# ProPrj_Thunder_F722_Final_2024-11-16.net
KiCad netlist of a schematic drawn in EasyEDA Pro
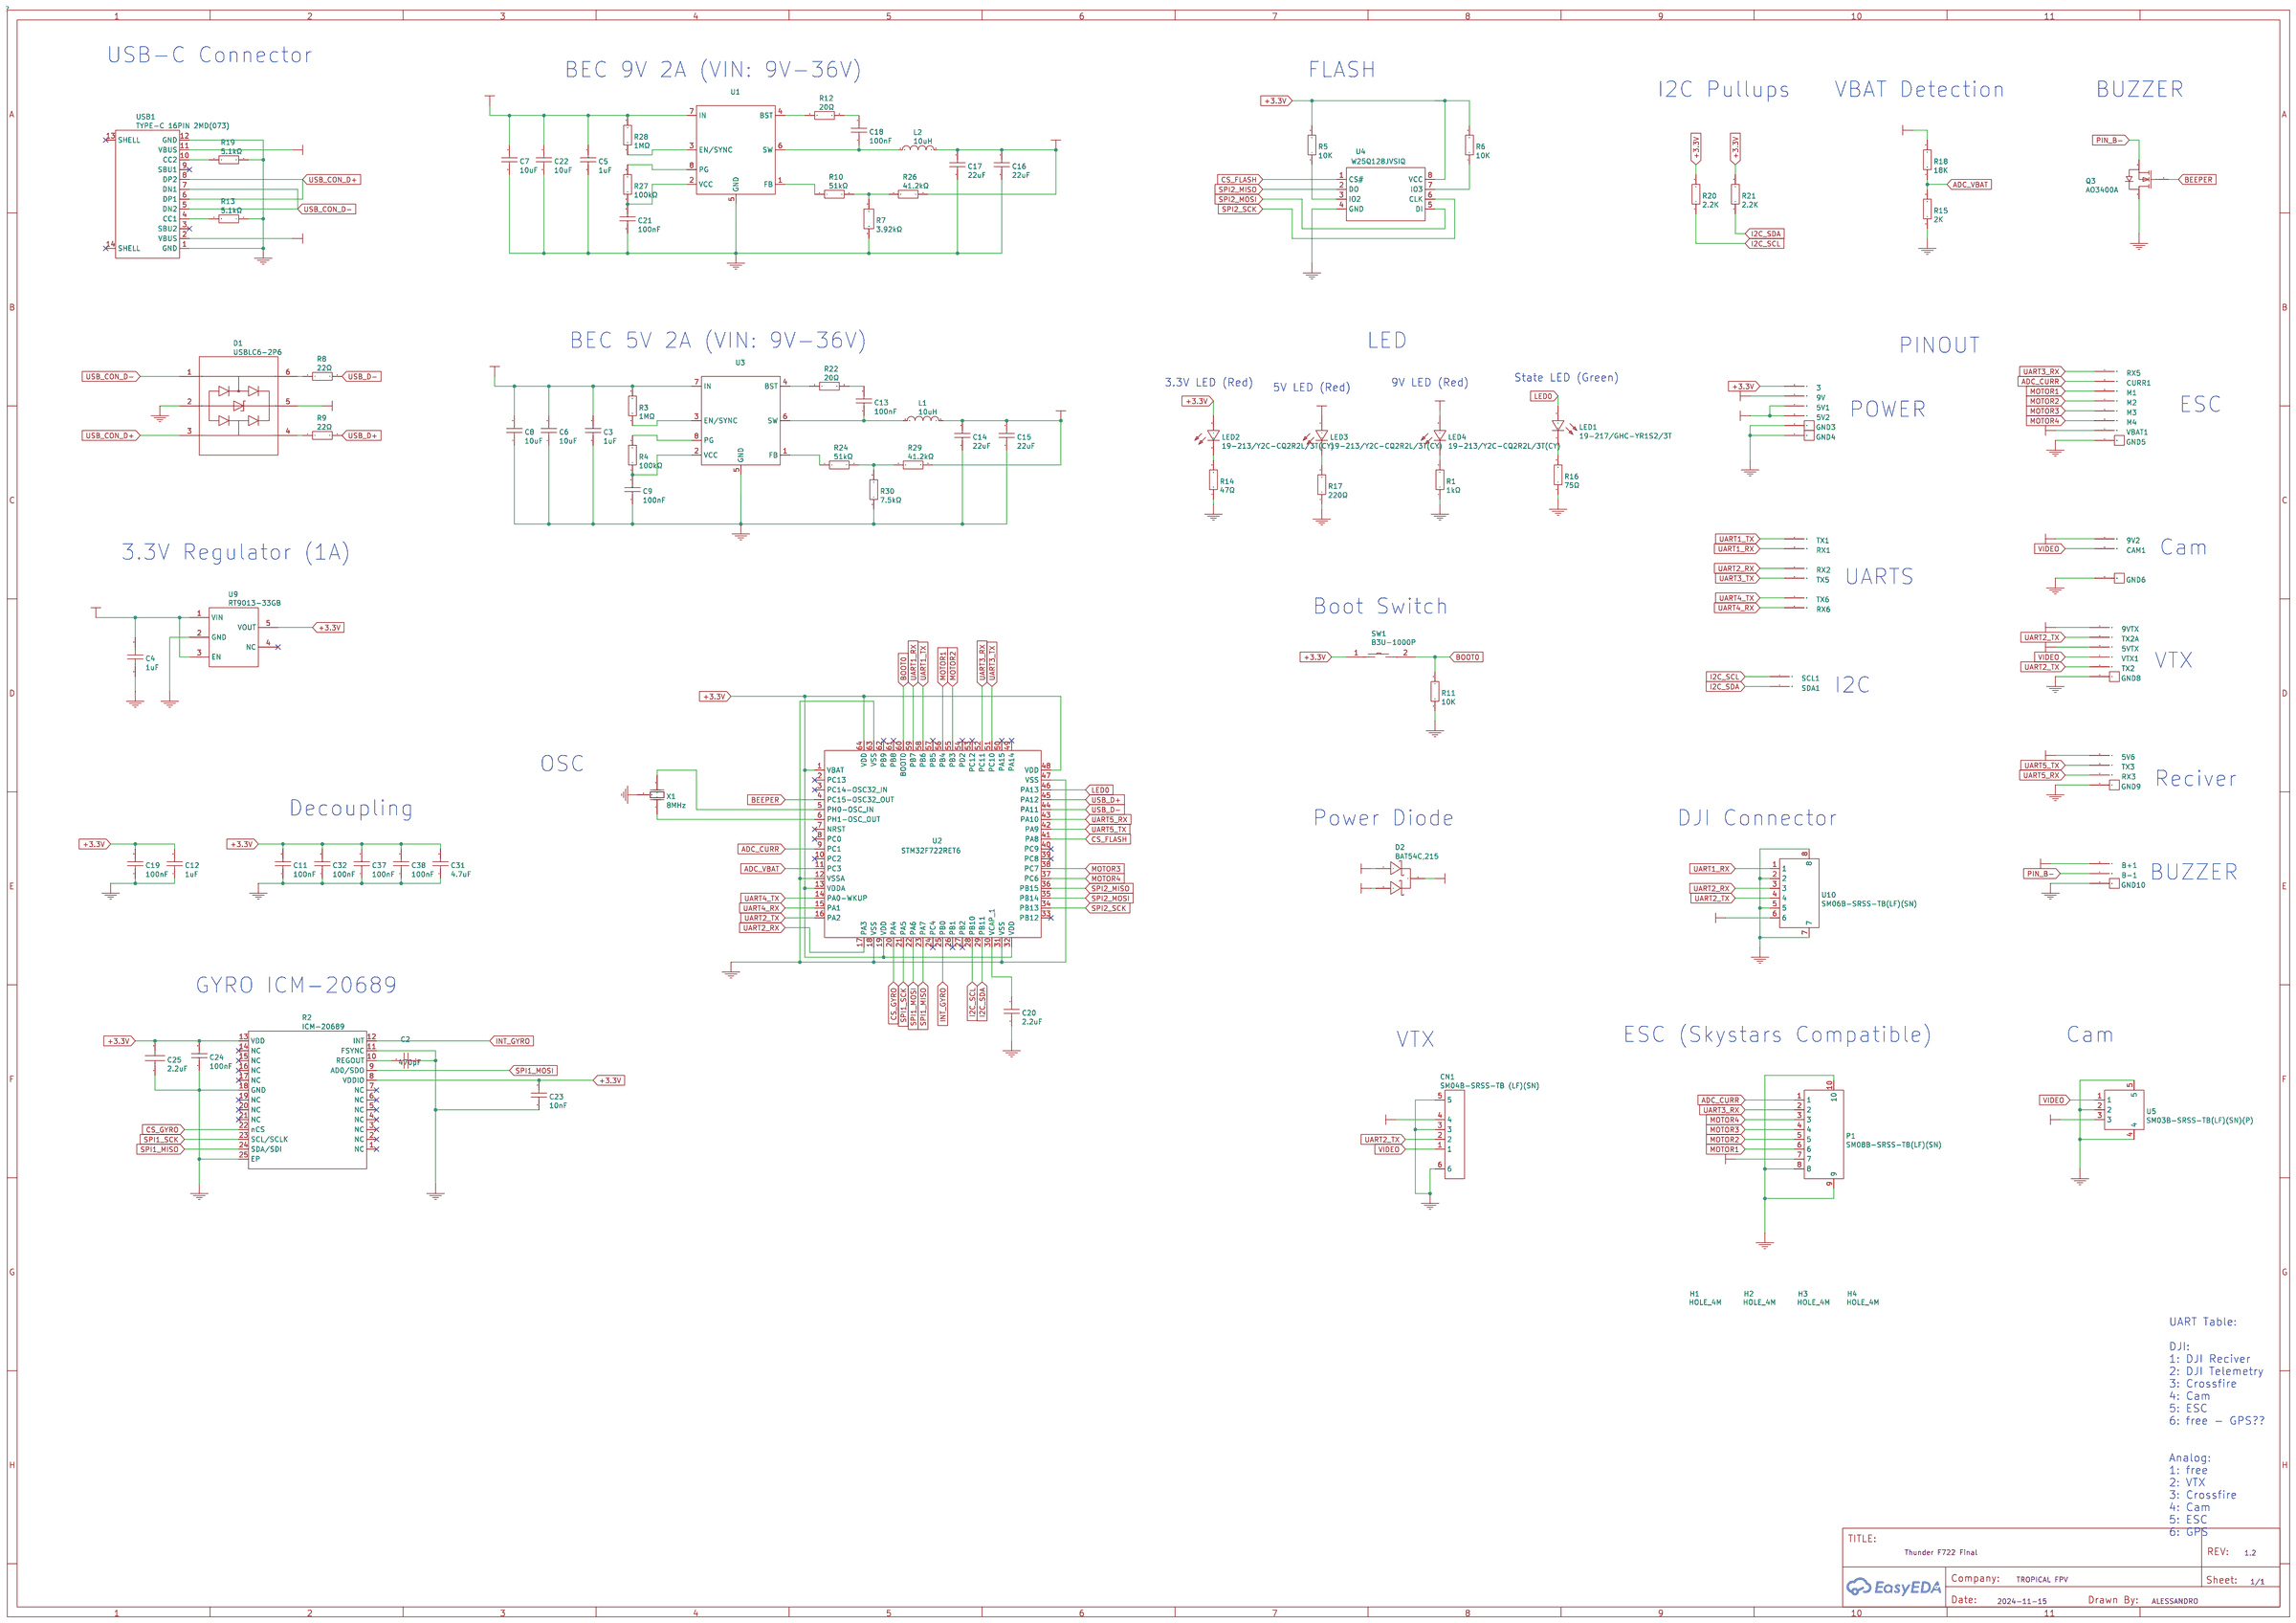
[diagram p0: schematic sheet]

(export (version "E")
  (design (tool "Eeschema 10.0.6"))
  (components
    (comp (ref "3")
      (value "ROUND SOLDER PADS WITH HOLE 1.5MM X 2.5MM COPY")
      (footprint "easyedapro:ROUND SOLDER PADS WITH HOLE 1MM X 1.75MM")
      (fields (field (name "Manufacturer Part") "solderpad"))
      (libsource (lib "easyedapro") (part "ROUND SOLDER PADS WITH HOLE 1.5MM X 2.5MM COPY"))
    )
    (comp (ref "5V1")
      (value "ROUND SOLDER PADS WITH HOLE 1.5MM X 2.5MM COPY")
      (footprint "easyedapro:ROUND SOLDER PADS WITH HOLE 1MM X 1.75MM")
      (fields (field (name "Manufacturer Part") "solderpad"))
      (libsource (lib "easyedapro") (part "ROUND SOLDER PADS WITH HOLE 1.5MM X 2.5MM COPY"))
    )
    (comp (ref "5V2")
      (value "ROUND SOLDER PADS WITH HOLE 1.5MM X 2.5MM COPY")
      (footprint "easyedapro:ROUND SOLDER PADS WITH HOLE 1MM X 1.75MM")
      (fields (field (name "Manufacturer Part") "solderpad"))
      (libsource (lib "easyedapro") (part "ROUND SOLDER PADS WITH HOLE 1.5MM X 2.5MM COPY"))
    )
    (comp (ref "5V6")
      (value "ROUND SOLDER PADS WITH HOLE 1.5MM X 2.5MM COPY")
      (footprint "easyedapro:ROUND SOLDER PADS WITH HOLE 1MM X 1.75MM")
      (fields (field (name "Manufacturer Part") "solderpad"))
      (libsource (lib "easyedapro") (part "ROUND SOLDER PADS WITH HOLE 1.5MM X 2.5MM COPY"))
    )
    (comp (ref "5VTX")
      (value "ROUND SOLDER PADS WITH HOLE 1.5MM X 2.5MM COPY")
      (footprint "easyedapro:ROUND SOLDER PADS WITH HOLE 1MM X 1.75MM")
      (fields (field (name "Manufacturer Part") "solderpad"))
      (libsource (lib "easyedapro") (part "ROUND SOLDER PADS WITH HOLE 1.5MM X 2.5MM COPY"))
    )
    (comp (ref "9V")
      (value "ROUND SOLDER PADS WITH HOLE 1.5MM X 2.5MM COPY")
      (footprint "easyedapro:ROUND SOLDER PADS WITH HOLE 1MM X 1.75MM")
      (fields (field (name "Manufacturer Part") "solderpad"))
      (libsource (lib "easyedapro") (part "ROUND SOLDER PADS WITH HOLE 1.5MM X 2.5MM COPY"))
    )
    (comp (ref "9V2")
      (value "ROUND SOLDER PADS WITH HOLE 1.5MM X 2.5MM COPY")
      (footprint "easyedapro:ROUND SOLDER PADS WITH HOLE 1MM X 1.75MM")
      (fields (field (name "Manufacturer Part") "solderpad"))
      (libsource (lib "easyedapro") (part "ROUND SOLDER PADS WITH HOLE 1.5MM X 2.5MM COPY"))
    )
    (comp (ref "9VTX")
      (value "ROUND SOLDER PADS WITH HOLE 1.5MM X 2.5MM COPY")
      (footprint "easyedapro:ROUND SOLDER PADS WITH HOLE 1MM X 1.75MM")
      (fields (field (name "Manufacturer Part") "solderpad"))
      (libsource (lib "easyedapro") (part "ROUND SOLDER PADS WITH HOLE 1.5MM X 2.5MM COPY"))
    )
    (comp (ref "B+1")
      (value "ROUND SOLDER PADS WITH HOLE 1.5MM X 2.5MM COPY")
      (footprint "easyedapro:ROUND SOLDER PADS WITH HOLE 1MM X 1.75MM")
      (fields (field (name "Manufacturer Part") "solderpad"))
      (libsource (lib "easyedapro") (part "ROUND SOLDER PADS WITH HOLE 1.5MM X 2.5MM COPY"))
    )
    (comp (ref "B-1")
      (value "ROUND SOLDER PADS WITH HOLE 1.5MM X 2.5MM COPY")
      (footprint "easyedapro:ROUND SOLDER PADS WITH HOLE 1MM X 1.75MM")
      (fields (field (name "Manufacturer Part") "solderpad"))
      (libsource (lib "easyedapro") (part "ROUND SOLDER PADS WITH HOLE 1.5MM X 2.5MM COPY"))
    )
    (comp (ref "C2")
      (value "470pF")
      (footprint "easyedapro:C0402")
      (fields (field (name "Manufacturer Part") "0402B471K500NT") (field (name "Manufacturer") "FH(风华)"))
      (libsource (lib "easyedapro") (part "470pF"))
    )
    (comp (ref "C3")
      (value "1uF")
      (footprint "easyedapro:C0603")
      (fields (field (name "Manufacturer Part") "CL10A105KB8NNNC") (field (name "Manufacturer") "SAMSUNG"))
      (libsource (lib "easyedapro") (part "1uF"))
    )
    (comp (ref "C4")
      (value "1uF")
      (footprint "easyedapro:C0402")
      (fields (field (name "Manufacturer Part") "CL05A105KA5NQNC") (field (name "Manufacturer") "SAMSUNG"))
      (libsource (lib "") (part "1uF_1"))
    )
    (comp (ref "C5")
      (value "1uF")
      (footprint "easyedapro:C0603")
      (fields (field (name "Manufacturer Part") "CL10A105KB8NNNC") (field (name "Manufacturer") "SAMSUNG"))
      (libsource (lib "easyedapro") (part "1uF"))
    )
    (comp (ref "C6")
      (value "10uF")
      (footprint "easyedapro:C1206")
      (fields (field (name "Manufacturer Part") "CL31A106KBHNNNE") (field (name "Manufacturer") "SAMSUNG"))
      (libsource (lib "easyedapro") (part "10uF"))
    )
    (comp (ref "C7")
      (value "10uF")
      (footprint "easyedapro:C1206")
      (fields (field (name "Manufacturer Part") "CL31A106KBHNNNE") (field (name "Manufacturer") "SAMSUNG"))
      (libsource (lib "easyedapro") (part "10uF"))
    )
    (comp (ref "C8")
      (value "10uF")
      (footprint "easyedapro:C1206")
      (fields (field (name "Manufacturer Part") "CL31A106KBHNNNE") (field (name "Manufacturer") "SAMSUNG"))
      (libsource (lib "easyedapro") (part "10uF"))
    )
    (comp (ref "C9")
      (value "100nF")
      (footprint "easyedapro:C0402")
      (fields (field (name "Manufacturer Part") "CL05B104KO5NNNC") (field (name "Manufacturer") "SAMSUNG"))
      (libsource (lib "easyedapro") (part "100nF"))
    )
    (comp (ref "C11")
      (value "100nF")
      (footprint "easyedapro:C0402")
      (fields (field (name "Manufacturer Part") "CL05B104KO5NNNC") (field (name "Manufacturer") "SAMSUNG"))
      (libsource (lib "easyedapro") (part "100nF"))
    )
    (comp (ref "C12")
      (value "1uF")
      (footprint "easyedapro:C0603")
      (fields (field (name "Manufacturer Part") "CL10A105KB8NNNC") (field (name "Manufacturer") "SAMSUNG"))
      (libsource (lib "easyedapro") (part "1uF"))
    )
    (comp (ref "C13")
      (value "100nF")
      (footprint "easyedapro:C0402")
      (fields (field (name "Manufacturer Part") "CL05B104KO5NNNC") (field (name "Manufacturer") "SAMSUNG"))
      (libsource (lib "easyedapro") (part "100nF"))
    )
    (comp (ref "C14")
      (value "22uF")
      (footprint "easyedapro:C1206")
      (fields
        (field (name "Manufacturer Part") "CL31A226KPHNNNE")
        (field (name "Manufacturer") "SAMSUNG(三星)")
      )
      (libsource (lib "easyedapro") (part "22uF"))
    )
    (comp (ref "C15")
      (value "22uF")
      (footprint "easyedapro:C1206")
      (fields
        (field (name "Manufacturer Part") "CL31A226KPHNNNE")
        (field (name "Manufacturer") "SAMSUNG(三星)")
      )
      (libsource (lib "easyedapro") (part "22uF"))
    )
    (comp (ref "C16")
      (value "22uF")
      (footprint "easyedapro:C1206")
      (fields
        (field (name "Manufacturer Part") "CL31A226KPHNNNE")
        (field (name "Manufacturer") "SAMSUNG(三星)")
      )
      (libsource (lib "easyedapro") (part "22uF"))
    )
    (comp (ref "C17")
      (value "22uF")
      (footprint "easyedapro:C1206")
      (fields
        (field (name "Manufacturer Part") "CL31A226KPHNNNE")
        (field (name "Manufacturer") "SAMSUNG(三星)")
      )
      (libsource (lib "easyedapro") (part "22uF"))
    )
    (comp (ref "C18")
      (value "100nF")
      (footprint "easyedapro:C0402")
      (fields (field (name "Manufacturer Part") "CL05B104KO5NNNC") (field (name "Manufacturer") "SAMSUNG"))
      (libsource (lib "easyedapro") (part "100nF"))
    )
    (comp (ref "C19")
      (value "100nF")
      (footprint "easyedapro:C0402")
      (fields (field (name "Manufacturer Part") "CL05B104KO5NNNC") (field (name "Manufacturer") "SAMSUNG"))
      (libsource (lib "easyedapro") (part "100nF"))
    )
    (comp (ref "C20")
      (value "2.2uF")
      (footprint "easyedapro:C0603")
      (fields (field (name "Manufacturer Part") "CL10A225KO8NNNC") (field (name "Manufacturer") "SAMSUNG"))
      (libsource (lib "easyedapro") (part "2.2uF"))
    )
    (comp (ref "C21")
      (value "100nF")
      (footprint "easyedapro:C0402")
      (fields (field (name "Manufacturer Part") "CL05B104KO5NNNC") (field (name "Manufacturer") "SAMSUNG"))
      (libsource (lib "easyedapro") (part "100nF"))
    )
    (comp (ref "C22")
      (value "10uF")
      (footprint "easyedapro:C1206")
      (fields (field (name "Manufacturer Part") "CL31A106KBHNNNE") (field (name "Manufacturer") "SAMSUNG"))
      (libsource (lib "easyedapro") (part "10uF"))
    )
    (comp (ref "C23")
      (value "10nF")
      (footprint "easyedapro:C0402")
      (fields
        (field (name "Manufacturer Part") "CL05B103KB5NNNC")
        (field (name "Manufacturer") "SAMSUNG(三星)")
      )
      (libsource (lib "easyedapro") (part "10nF"))
    )
    (comp (ref "C24")
      (value "100nF")
      (footprint "easyedapro:C0402")
      (fields (field (name "Manufacturer Part") "CL05B104KO5NNNC") (field (name "Manufacturer") "SAMSUNG"))
      (libsource (lib "easyedapro") (part "100nF"))
    )
    (comp (ref "C25")
      (value "2.2uF")
      (footprint "easyedapro:C0402")
      (fields
        (field (name "Manufacturer Part") "CL05A225MQ5NSNC")
        (field (name "Manufacturer") "SAMSUNG(三星)")
      )
      (libsource (lib "") (part "2.2uF_1"))
    )
    (comp (ref "C31")
      (value "4.7uF")
      (footprint "easyedapro:C0603")
      (fields (field (name "Manufacturer Part") "CL10A475KO8NNNC") (field (name "Manufacturer") "SAMSUNG"))
      (libsource (lib "easyedapro") (part "4.7uF"))
    )
    (comp (ref "C32")
      (value "100nF")
      (footprint "easyedapro:C0402")
      (fields (field (name "Manufacturer Part") "CL05B104KO5NNNC") (field (name "Manufacturer") "SAMSUNG"))
      (libsource (lib "easyedapro") (part "100nF"))
    )
    (comp (ref "C37")
      (value "100nF")
      (footprint "easyedapro:C0402")
      (fields (field (name "Manufacturer Part") "CL05B104KO5NNNC") (field (name "Manufacturer") "SAMSUNG"))
      (libsource (lib "easyedapro") (part "100nF"))
    )
    (comp (ref "C38")
      (value "100nF")
      (footprint "easyedapro:C0402")
      (fields (field (name "Manufacturer Part") "CL05B104KO5NNNC") (field (name "Manufacturer") "SAMSUNG"))
      (libsource (lib "easyedapro") (part "100nF"))
    )
    (comp (ref "CAM1")
      (value "ROUND SOLDER PADS WITH HOLE 1.5MM X 2.5MM COPY")
      (footprint "easyedapro:ROUND SOLDER PADS WITH HOLE 1MM X 1.75MM")
      (fields (field (name "Manufacturer Part") "solderpad"))
      (libsource (lib "easyedapro") (part "ROUND SOLDER PADS WITH HOLE 1.5MM X 2.5MM COPY"))
    )
    (comp (ref "CN1")
      (value "SM04B-SRSS-TB (LF)(SN)")
      (footprint "easyedapro:CONN-SMD_4P-P1.00_SM04B-SRSS-TB-LF-SN")
      (fields (field (name "Manufacturer Part") "SM04B-SRSS-TB(LF)(SN)") (field (name "Manufacturer") "JST"))
      (libsource (lib "easyedapro") (part "SM04B-SRSS-TB (LF)(SN)"))
    )
    (comp (ref "CURR1")
      (value "ROUND SOLDER PADS WITH HOLE 1.5MM X 2.5MM COPY")
      (footprint "easyedapro:ROUND SOLDER PADS WITH HOLE 1MM X 1.75MM")
      (fields (field (name "Manufacturer Part") "solderpad"))
      (libsource (lib "easyedapro") (part "ROUND SOLDER PADS WITH HOLE 1.5MM X 2.5MM COPY"))
    )
    (comp (ref "D1")
      (value "USBLC6-2P6")
      (footprint "easyedapro:SOT-666-6_L1.6-W1.2-P0.50-LS1.6-BR")
      (fields (field (name "Manufacturer") "STMicroelectronics"))
      (libsource (lib "easyedapro") (part "USBLC6-2P6"))
    )
    (comp (ref "D2")
      (value "BAT54C,215")
      (footprint "easyedapro:SOT-23-3_L2.9-W1.6-P1.90-LS2.8-BR")
      (fields (field (name "Manufacturer") "Nexperia(安世)"))
      (libsource (lib "easyedapro") (part "BAT54C,215"))
    )
    (comp (ref "GND3")
      (value "RECTANGLE SOLDER PADS WITH HOLE 1.5MM X 2.5MM")
      (footprint "easyedapro:RECTANGLE SOLDER PADS WITH HOLE 1.25MM X 1.75MM")
      (fields (field (name "Manufacturer Part") "solderpad"))
      (libsource (lib "easyedapro") (part "RECTANGLE SOLDER PADS WITH HOLE 1.5MM X 2.5MM"))
    )
    (comp (ref "GND4")
      (value "RECTANGLE SOLDER PADS WITH HOLE 1.5MM X 2.5MM")
      (footprint "easyedapro:RECTANGLE SOLDER PADS WITH HOLE 1.25MM X 1.75MM")
      (fields (field (name "Manufacturer Part") "solderpad"))
      (libsource (lib "easyedapro") (part "RECTANGLE SOLDER PADS WITH HOLE 1.5MM X 2.5MM"))
    )
    (comp (ref "GND5")
      (value "RECTANGLE SOLDER PADS WITH HOLE 1.5MM X 2.5MM")
      (footprint "easyedapro:RECTANGLE SOLDER PADS WITH HOLE 1.25MM X 1.75MM")
      (fields (field (name "Manufacturer Part") "solderpad"))
      (libsource (lib "easyedapro") (part "RECTANGLE SOLDER PADS WITH HOLE 1.5MM X 2.5MM"))
    )
    (comp (ref "GND6")
      (value "RECTANGLE SOLDER PADS WITH HOLE 1.5MM X 2.5MM")
      (footprint "easyedapro:RECTANGLE SOLDER PADS WITH HOLE 1.25MM X 1.75MM")
      (fields (field (name "Manufacturer Part") "solderpad"))
      (libsource (lib "easyedapro") (part "RECTANGLE SOLDER PADS WITH HOLE 1.5MM X 2.5MM"))
    )
    (comp (ref "GND8")
      (value "RECTANGLE SOLDER PADS WITH HOLE 1.5MM X 2.5MM")
      (footprint "easyedapro:RECTANGLE SOLDER PADS WITH HOLE 1.25MM X 1.75MM")
      (fields (field (name "Manufacturer Part") "solderpad"))
      (libsource (lib "easyedapro") (part "RECTANGLE SOLDER PADS WITH HOLE 1.5MM X 2.5MM"))
    )
    (comp (ref "GND9")
      (value "RECTANGLE SOLDER PADS WITH HOLE 1.5MM X 2.5MM")
      (footprint "easyedapro:RECTANGLE SOLDER PADS WITH HOLE 1.25MM X 1.75MM")
      (fields (field (name "Manufacturer Part") "solderpad"))
      (libsource (lib "easyedapro") (part "RECTANGLE SOLDER PADS WITH HOLE 1.5MM X 2.5MM"))
    )
    (comp (ref "GND10")
      (value "RECTANGLE SOLDER PADS WITH HOLE 1.5MM X 2.5MM")
      (footprint "easyedapro:RECTANGLE SOLDER PADS WITH HOLE 1.25MM X 1.75MM")
      (fields (field (name "Manufacturer Part") "solderpad"))
      (libsource (lib "easyedapro") (part "RECTANGLE SOLDER PADS WITH HOLE 1.5MM X 2.5MM"))
    )
    (comp (ref "H1")
      (value "HOLE_4M")
      (footprint "easyedapro:HOLE_4MM")
      (libsource (lib "easyedapro") (part "HOLE_4M"))
    )
    (comp (ref "H2")
      (value "HOLE_4M")
      (footprint "easyedapro:HOLE_4MM")
      (libsource (lib "easyedapro") (part "HOLE_4M"))
    )
    (comp (ref "H3")
      (value "HOLE_4M")
      (footprint "easyedapro:HOLE_4MM")
      (libsource (lib "easyedapro") (part "HOLE_4M"))
    )
    (comp (ref "H4")
      (value "HOLE_4M")
      (footprint "easyedapro:HOLE_4MM")
      (libsource (lib "easyedapro") (part "HOLE_4M"))
    )
    (comp (ref "L1")
      (value "10uH")
      (footprint "easyedapro:IND-SMD_L4.4-W4.2_PSPMAA0412")
      (fields (field (name "Manufacturer Part") "YSPI0420-100M") (field (name "Manufacturer") "YJYCOIN(益嘉源)"))
      (libsource (lib "easyedapro") (part "10uH"))
    )
    (comp (ref "L2")
      (value "10uH")
      (footprint "easyedapro:IND-SMD_L4.4-W4.2_PSPMAA0412")
      (fields (field (name "Manufacturer Part") "YSPI0420-100M") (field (name "Manufacturer") "YJYCOIN(益嘉源)"))
      (libsource (lib "easyedapro") (part "10uH"))
    )
    (comp (ref "LED1")
      (value "19-217/GHC-YR1S2/3T")
      (footprint "easyedapro:LED0603-R-RD")
      (fields (field (name "Manufacturer") "EVERLIGHT"))
      (libsource (lib "easyedapro") (part "19-217/GHC-YR1S2/3T"))
    )
    (comp (ref "LED2")
      (value "19-213/Y2C-CQ2R2L/3T(CY)")
      (footprint "easyedapro:LED0603-RD-YELLOW")
      (fields (field (name "Manufacturer") "EVERLIGHT(亿光)"))
      (libsource (lib "easyedapro") (part "19-213/Y2C-CQ2R2L/3T(CY)"))
    )
    (comp (ref "LED3")
      (value "19-213/Y2C-CQ2R2L/3T(CY)")
      (footprint "easyedapro:LED0603-RD-YELLOW")
      (fields (field (name "Manufacturer") "EVERLIGHT(亿光)"))
      (libsource (lib "easyedapro") (part "19-213/Y2C-CQ2R2L/3T(CY)"))
    )
    (comp (ref "LED4")
      (value "19-213/Y2C-CQ2R2L/3T(CY)")
      (footprint "easyedapro:LED0603-RD-YELLOW")
      (fields (field (name "Manufacturer") "EVERLIGHT(亿光)"))
      (libsource (lib "easyedapro") (part "19-213/Y2C-CQ2R2L/3T(CY)"))
    )
    (comp (ref "M1")
      (value "ROUND SOLDER PADS WITH HOLE 1.5MM X 2.5MM COPY")
      (footprint "easyedapro:ROUND SOLDER PADS WITH HOLE 1MM X 1.75MM")
      (fields (field (name "Manufacturer Part") "solderpad"))
      (libsource (lib "easyedapro") (part "ROUND SOLDER PADS WITH HOLE 1.5MM X 2.5MM COPY"))
    )
    (comp (ref "M2")
      (value "ROUND SOLDER PADS WITH HOLE 1.5MM X 2.5MM COPY")
      (footprint "easyedapro:ROUND SOLDER PADS WITH HOLE 1MM X 1.75MM")
      (fields (field (name "Manufacturer Part") "solderpad"))
      (libsource (lib "easyedapro") (part "ROUND SOLDER PADS WITH HOLE 1.5MM X 2.5MM COPY"))
    )
    (comp (ref "M3")
      (value "ROUND SOLDER PADS WITH HOLE 1.5MM X 2.5MM COPY")
      (footprint "easyedapro:ROUND SOLDER PADS WITH HOLE 1MM X 1.75MM")
      (fields (field (name "Manufacturer Part") "solderpad"))
      (libsource (lib "easyedapro") (part "ROUND SOLDER PADS WITH HOLE 1.5MM X 2.5MM COPY"))
    )
    (comp (ref "M4")
      (value "ROUND SOLDER PADS WITH HOLE 1.5MM X 2.5MM COPY")
      (footprint "easyedapro:ROUND SOLDER PADS WITH HOLE 1MM X 1.75MM")
      (fields (field (name "Manufacturer Part") "solderpad"))
      (libsource (lib "easyedapro") (part "ROUND SOLDER PADS WITH HOLE 1.5MM X 2.5MM COPY"))
    )
    (comp (ref "P1")
      (value "SM08B-SRSS-TB(LF)(SN)")
      (footprint "easyedapro:CONN-TH_SM08B-SRSS-TB-LF-SN")
      (fields (field (name "Manufacturer") "JST"))
      (libsource (lib "easyedapro") (part "SM08B-SRSS-TB(LF)(SN)"))
    )
    (comp (ref "Q3")
      (value "AO3400A")
      (footprint "easyedapro:SOT-23-3_L2.9-W1.6-P1.90-LS2.8-BR")
      (fields (field (name "Manufacturer") "AOS"))
      (libsource (lib "easyedapro") (part "AO3400A"))
    )
    (comp (ref "R1")
      (value "1kΩ")
      (footprint "easyedapro:R0603")
      (fields
        (field (name "Manufacturer Part") "0603WAF1001T5E")
        (field (name "Manufacturer") "UNI-ROYAL(厚声)")
      )
      (libsource (lib "easyedapro") (part "1kΩ"))
    )
    (comp (ref "R2")
      (value "ICM-20689")
      (footprint "easyedapro:QFN-24_L4.0-W4.0-P0.50-TL-EP2.6")
      (fields (field (name "Manufacturer") "TDK InvenSense(应美盛)"))
      (libsource (lib "easyedapro") (part "ICM-20689"))
    )
    (comp (ref "R3")
      (value "1MΩ")
      (footprint "easyedapro:R0603")
      (fields
        (field (name "Manufacturer Part") "0603WAF1004T5E")
        (field (name "Manufacturer") "UNI-ROYAL(厚声)")
      )
      (libsource (lib "easyedapro") (part "1MΩ"))
    )
    (comp (ref "R4")
      (value "100kΩ")
      (footprint "easyedapro:R0402")
      (fields
        (field (name "Manufacturer Part") "0402WGF1003TCE")
        (field (name "Manufacturer") "UNI-ROYAL(厚声)")
      )
      (libsource (lib "easyedapro") (part "100kΩ"))
    )
    (comp (ref "R5")
      (value "10K")
      (footprint "easyedapro:R0402")
      (fields (field (name "Manufacturer Part") "0402WGF1002TCE") (field (name "Manufacturer") "UniOhm"))
      (libsource (lib "easyedapro") (part "10K"))
    )
    (comp (ref "R6")
      (value "10K")
      (footprint "easyedapro:R0402")
      (fields (field (name "Manufacturer Part") "0402WGF1002TCE") (field (name "Manufacturer") "UniOhm"))
      (libsource (lib "easyedapro") (part "10K"))
    )
    (comp (ref "R7")
      (value "3.92kΩ")
      (footprint "easyedapro:R1206")
      (fields
        (field (name "Manufacturer Part") "1206W4F3921T5E")
        (field (name "Manufacturer") "UNI-ROYAL(厚声)")
      )
      (libsource (lib "easyedapro") (part "3.92kΩ"))
    )
    (comp (ref "R8")
      (value "22Ω")
      (footprint "easyedapro:R0402")
      (fields
        (field (name "Manufacturer Part") "0402WGF220JTCE")
        (field (name "Manufacturer") "UNI-ROYAL(厚声)")
      )
      (libsource (lib "easyedapro") (part "22Ω"))
    )
    (comp (ref "R9")
      (value "22Ω")
      (footprint "easyedapro:R0402")
      (fields
        (field (name "Manufacturer Part") "0402WGF220JTCE")
        (field (name "Manufacturer") "UNI-ROYAL(厚声)")
      )
      (libsource (lib "easyedapro") (part "22Ω"))
    )
    (comp (ref "R10")
      (value "51kΩ")
      (footprint "easyedapro:R0402")
      (fields
        (field (name "Manufacturer Part") "0402WGF5102TCE")
        (field (name "Manufacturer") "UNI-ROYAL(厚声)")
      )
      (libsource (lib "easyedapro") (part "51kΩ"))
    )
    (comp (ref "R11")
      (value "10K")
      (footprint "easyedapro:R0402")
      (fields (field (name "Manufacturer Part") "0402WGF1002TCE") (field (name "Manufacturer") "UniOhm"))
      (libsource (lib "easyedapro") (part "10K"))
    )
    (comp (ref "R12")
      (value "20Ω")
      (footprint "easyedapro:R0603")
      (fields
        (field (name "Manufacturer Part") "0603WAF200JT5E")
        (field (name "Manufacturer") "UNI-ROYAL(厚声)")
      )
      (libsource (lib "easyedapro") (part "20Ω"))
    )
    (comp (ref "R13")
      (value "5.1kΩ")
      (footprint "easyedapro:R0402")
      (fields
        (field (name "Manufacturer Part") "0402WGF5101TCE")
        (field (name "Manufacturer") "UNI-ROYAL(厚声)")
      )
      (libsource (lib "easyedapro") (part "5.1kΩ"))
    )
    (comp (ref "R14")
      (value "47Ω")
      (footprint "easyedapro:R0402")
      (fields (field (name "Manufacturer Part") "0402WGF470JTCE") (field (name "Manufacturer") "UniOhm"))
      (libsource (lib "easyedapro") (part "47Ω"))
    )
    (comp (ref "R15")
      (value "2K")
      (footprint "easyedapro:R0402")
      (fields (field (name "Manufacturer Part") "0402WGF2001TCE") (field (name "Manufacturer") "UniOhm"))
      (libsource (lib "easyedapro") (part "2K"))
    )
    (comp (ref "R16")
      (value "75Ω")
      (footprint "easyedapro:R0603")
      (fields (field (name "Manufacturer Part") "0603WAF750JT5E") (field (name "Manufacturer") "UniOhm"))
      (libsource (lib "easyedapro") (part "75Ω"))
    )
    (comp (ref "R17")
      (value "220Ω")
      (footprint "easyedapro:R0402")
      (fields (field (name "Manufacturer Part") "0402WGF2200TCE") (field (name "Manufacturer") "UniOhm"))
      (libsource (lib "easyedapro") (part "220Ω"))
    )
    (comp (ref "R18")
      (value "18K")
      (footprint "easyedapro:R0402")
      (fields (field (name "Manufacturer Part") "0402WGF1802TCE") (field (name "Manufacturer") "UniOhm"))
      (libsource (lib "easyedapro") (part "18K"))
    )
    (comp (ref "R19")
      (value "5.1kΩ")
      (footprint "easyedapro:R0402")
      (fields
        (field (name "Manufacturer Part") "0402WGF5101TCE")
        (field (name "Manufacturer") "UNI-ROYAL(厚声)")
      )
      (libsource (lib "easyedapro") (part "5.1kΩ"))
    )
    (comp (ref "R20")
      (value "2.2K")
      (footprint "easyedapro:R0402")
      (fields (field (name "Manufacturer Part") "0402WGF2201TCE") (field (name "Manufacturer") "UniOhm"))
      (libsource (lib "easyedapro") (part "2.2K"))
    )
    (comp (ref "R21")
      (value "2.2K")
      (footprint "easyedapro:R0402")
      (fields (field (name "Manufacturer Part") "0402WGF2201TCE") (field (name "Manufacturer") "UniOhm"))
      (libsource (lib "easyedapro") (part "2.2K"))
    )
    (comp (ref "R22")
      (value "20Ω")
      (footprint "easyedapro:R0603")
      (fields
        (field (name "Manufacturer Part") "0603WAF200JT5E")
        (field (name "Manufacturer") "UNI-ROYAL(厚声)")
      )
      (libsource (lib "easyedapro") (part "20Ω"))
    )
    (comp (ref "R24")
      (value "51kΩ")
      (footprint "easyedapro:R0402")
      (fields
        (field (name "Manufacturer Part") "0402WGF5102TCE")
        (field (name "Manufacturer") "UNI-ROYAL(厚声)")
      )
      (libsource (lib "easyedapro") (part "51kΩ"))
    )
    (comp (ref "R26")
      (value "41.2kΩ")
      (footprint "easyedapro:R1206")
      (fields (field (name "Manufacturer Part") "RS-06K4122FT") (field (name "Manufacturer") "FH(风华)"))
      (libsource (lib "easyedapro") (part "41.2kΩ"))
    )
    (comp (ref "R27")
      (value "100kΩ")
      (footprint "easyedapro:R0402")
      (fields
        (field (name "Manufacturer Part") "0402WGF1003TCE")
        (field (name "Manufacturer") "UNI-ROYAL(厚声)")
      )
      (libsource (lib "easyedapro") (part "100kΩ"))
    )
    (comp (ref "R28")
      (value "1MΩ")
      (footprint "easyedapro:R0603")
      (fields
        (field (name "Manufacturer Part") "0603WAF1004T5E")
        (field (name "Manufacturer") "UNI-ROYAL(厚声)")
      )
      (libsource (lib "easyedapro") (part "1MΩ"))
    )
    (comp (ref "R29")
      (value "41.2kΩ")
      (footprint "easyedapro:R1206")
      (fields (field (name "Manufacturer Part") "RS-06K4122FT") (field (name "Manufacturer") "FH(风华)"))
      (libsource (lib "easyedapro") (part "41.2kΩ"))
    )
    (comp (ref "R30")
      (value "7.5kΩ")
      (footprint "easyedapro:R0402")
      (fields
        (field (name "Manufacturer Part") "0402WGF7501TCE")
        (field (name "Manufacturer") "UNI-ROYAL(厚声)")
      )
      (libsource (lib "easyedapro") (part "7.5kΩ"))
    )
    (comp (ref "RX1")
      (value "ROUND SOLDER PADS WITH HOLE 1.5MM X 2.5MM COPY")
      (footprint "easyedapro:ROUND SOLDER PADS WITH HOLE 1MM X 1.75MM")
      (fields (field (name "Manufacturer Part") "solderpad"))
      (libsource (lib "easyedapro") (part "ROUND SOLDER PADS WITH HOLE 1.5MM X 2.5MM COPY"))
    )
    (comp (ref "RX2")
      (value "ROUND SOLDER PADS WITH HOLE 1.5MM X 2.5MM COPY")
      (footprint "easyedapro:ROUND SOLDER PADS WITH HOLE 1MM X 1.75MM")
      (fields (field (name "Manufacturer Part") "solderpad"))
      (libsource (lib "easyedapro") (part "ROUND SOLDER PADS WITH HOLE 1.5MM X 2.5MM COPY"))
    )
    (comp (ref "RX3")
      (value "ROUND SOLDER PADS WITH HOLE 1.5MM X 2.5MM COPY")
      (footprint "easyedapro:ROUND SOLDER PADS WITH HOLE 1MM X 1.75MM")
      (fields (field (name "Manufacturer Part") "solderpad"))
      (libsource (lib "easyedapro") (part "ROUND SOLDER PADS WITH HOLE 1.5MM X 2.5MM COPY"))
    )
    (comp (ref "RX5")
      (value "ROUND SOLDER PADS WITH HOLE 1.5MM X 2.5MM COPY")
      (footprint "easyedapro:ROUND SOLDER PADS WITH HOLE 1MM X 1.75MM")
      (fields (field (name "Manufacturer Part") "solderpad"))
      (libsource (lib "easyedapro") (part "ROUND SOLDER PADS WITH HOLE 1.5MM X 2.5MM COPY"))
    )
    (comp (ref "RX6")
      (value "ROUND SOLDER PADS WITH HOLE 1.5MM X 2.5MM COPY")
      (footprint "easyedapro:ROUND SOLDER PADS WITH HOLE 1MM X 1.75MM")
      (fields (field (name "Manufacturer Part") "solderpad"))
      (libsource (lib "easyedapro") (part "ROUND SOLDER PADS WITH HOLE 1.5MM X 2.5MM COPY"))
    )
    (comp (ref "SCL1")
      (value "ROUND SOLDER PADS WITH HOLE 1.5MM X 2.5MM COPY")
      (footprint "easyedapro:ROUND SOLDER PADS WITH HOLE 1MM X 1.75MM")
      (fields (field (name "Manufacturer Part") "solderpad"))
      (libsource (lib "easyedapro") (part "ROUND SOLDER PADS WITH HOLE 1.5MM X 2.5MM COPY"))
    )
    (comp (ref "SDA1")
      (value "ROUND SOLDER PADS WITH HOLE 1.5MM X 2.5MM COPY")
      (footprint "easyedapro:ROUND SOLDER PADS WITH HOLE 1MM X 1.75MM")
      (fields (field (name "Manufacturer Part") "solderpad"))
      (libsource (lib "easyedapro") (part "ROUND SOLDER PADS WITH HOLE 1.5MM X 2.5MM COPY"))
    )
    (comp (ref "SW1")
      (value "B3U-1000P")
      (footprint "easyedapro:KEY-SMD_B3U-1000PM")
      (fields (field (name "Manufacturer") "OMRON(欧姆龙)"))
      (libsource (lib "easyedapro") (part "B3U-1000P"))
    )
    (comp (ref "TX1")
      (value "ROUND SOLDER PADS WITH HOLE 1.5MM X 2.5MM COPY")
      (footprint "easyedapro:ROUND SOLDER PADS WITH HOLE 1MM X 1.75MM")
      (fields (field (name "Manufacturer Part") "solderpad"))
      (libsource (lib "easyedapro") (part "ROUND SOLDER PADS WITH HOLE 1.5MM X 2.5MM COPY"))
    )
    (comp (ref "TX2")
      (value "ROUND SOLDER PADS WITH HOLE 1.5MM X 2.5MM COPY")
      (footprint "easyedapro:ROUND SOLDER PADS WITH HOLE 1MM X 1.75MM")
      (fields (field (name "Manufacturer Part") "solderpad"))
      (libsource (lib "easyedapro") (part "ROUND SOLDER PADS WITH HOLE 1.5MM X 2.5MM COPY"))
    )
    (comp (ref "TX2A")
      (value "ROUND SOLDER PADS WITH HOLE 1.5MM X 2.5MM COPY")
      (footprint "easyedapro:ROUND SOLDER PADS WITH HOLE 1MM X 1.75MM")
      (fields (field (name "Manufacturer Part") "solderpad"))
      (libsource (lib "easyedapro") (part "ROUND SOLDER PADS WITH HOLE 1.5MM X 2.5MM COPY"))
    )
    (comp (ref "TX3")
      (value "ROUND SOLDER PADS WITH HOLE 1.5MM X 2.5MM COPY")
      (footprint "easyedapro:ROUND SOLDER PADS WITH HOLE 1MM X 1.75MM")
      (fields (field (name "Manufacturer Part") "solderpad"))
      (libsource (lib "easyedapro") (part "ROUND SOLDER PADS WITH HOLE 1.5MM X 2.5MM COPY"))
    )
    (comp (ref "TX5")
      (value "ROUND SOLDER PADS WITH HOLE 1.5MM X 2.5MM COPY")
      (footprint "easyedapro:ROUND SOLDER PADS WITH HOLE 1MM X 1.75MM")
      (fields (field (name "Manufacturer Part") "solderpad"))
      (libsource (lib "easyedapro") (part "ROUND SOLDER PADS WITH HOLE 1.5MM X 2.5MM COPY"))
    )
    (comp (ref "TX6")
      (value "ROUND SOLDER PADS WITH HOLE 1.5MM X 2.5MM COPY")
      (footprint "easyedapro:ROUND SOLDER PADS WITH HOLE 1MM X 1.75MM")
      (fields (field (name "Manufacturer Part") "solderpad"))
      (libsource (lib "easyedapro") (part "ROUND SOLDER PADS WITH HOLE 1.5MM X 2.5MM COPY"))
    )
    (comp (ref "U1")
      (value "NO")
      (footprint "easyedapro:QFN-8_L3.0-W3.0-P0.65-BL")
      (fields (field (name "Manufacturer Part") "MP9943GQ-Z"))
      (libsource (lib "easyedapro") (part "NO"))
    )
    (comp (ref "U2")
      (value "STM32F722RET6")
      (footprint "easyedapro:LQFP-64_L10.0-W10.0-P0.50-LS12.0-BL")
      (fields (field (name "Manufacturer") "STMicroelectronics"))
      (libsource (lib "easyedapro") (part "STM32F722RET6"))
    )
    (comp (ref "U3")
      (value "NO")
      (footprint "easyedapro:QFN-8_L3.0-W3.0-P0.65-BL")
      (fields (field (name "Manufacturer Part") "MP9943GQ-Z"))
      (libsource (lib "easyedapro") (part "NO"))
    )
    (comp (ref "U4")
      (value "W25Q128JVSIQ")
      (footprint "easyedapro:SOIC-8_L5.3-W5.3-P1.27-LS8.0-BL")
      (fields (field (name "Manufacturer") "WINBOND"))
      (libsource (lib "easyedapro") (part "W25Q128JVSIQ"))
    )
    (comp (ref "U5")
      (value "SM03B-SRSS-TB(LF)(SN)(P)")
      (footprint "easyedapro:CONN-SMD_SM03B-SRSS-TB-LF-SN-P")
      (fields (field (name "Manufacturer Part") "SM03B-SRSS-TB(LF)(SN)") (field (name "Manufacturer") "JST"))
      (libsource (lib "easyedapro") (part "SM03B-SRSS-TB(LF)(SN)(P)"))
    )
    (comp (ref "U9")
      (value "RT9013-33GB")
      (footprint "easyedapro:SOT-23-5_L3.0-W1.7-P0.95-LS2.8-BR")
      (fields (field (name "Manufacturer") "RICHTEK"))
      (libsource (lib "easyedapro") (part "RT9013-33GB"))
    )
    (comp (ref "U10")
      (value "SM06B-SRSS-TB(LF)(SN)")
      (footprint "easyedapro:CONN-SMD_SM06B-SRSS-TB(LF)(SN)")
      (fields (field (name "Manufacturer") "JST Sales America"))
      (libsource (lib "easyedapro") (part "SM06B-SRSS-TB(LF)(SN)"))
    )
    (comp (ref "USB1")
      (value "TYPE-C 16PIN 2MD(073)")
      (footprint "easyedapro:USB-C-SMD_TYPE-C-6PIN-2MD-073")
      (fields (field (name "Manufacturer") "SHOU HAN(首韩)"))
      (libsource (lib "easyedapro") (part "TYPE-C 16PIN 2MD(073)"))
    )
    (comp (ref "VBAT1")
      (value "ROUND SOLDER PADS WITH HOLE 1.5MM X 2.5MM COPY")
      (footprint "easyedapro:ROUND SOLDER PADS WITH HOLE 1MM X 1.75MM")
      (fields (field (name "Manufacturer Part") "solderpad"))
      (libsource (lib "easyedapro") (part "ROUND SOLDER PADS WITH HOLE 1.5MM X 2.5MM COPY"))
    )
    (comp (ref "VTX1")
      (value "ROUND SOLDER PADS WITH HOLE 1.5MM X 2.5MM COPY")
      (footprint "easyedapro:ROUND SOLDER PADS WITH HOLE 1MM X 1.75MM")
      (fields (field (name "Manufacturer Part") "solderpad"))
      (libsource (lib "easyedapro") (part "ROUND SOLDER PADS WITH HOLE 1.5MM X 2.5MM COPY"))
    )
    (comp (ref "X1")
      (value "8MHz")
      (footprint "easyedapro:OSC-SMD_3P-L3.2-W1.3-P1.20-L")
      (fields
        (field (name "Manufacturer Part") "CSTNE8M00G550000R0")
        (field (name "Manufacturer") "muRata(村田)")
      )
      (libsource (lib "easyedapro") (part "8MHz"))
    )
  )
  (nets
    (net (code "1") (name "+3.3V") (class "Default")
      (node (ref "3") (pin "1") (pinfunction "pad_1") (pintype "unspecified"))
      (node (ref "C11") (pin "2") (pinfunction "2_2") (pintype "input"))
      (node (ref "C12") (pin "2") (pinfunction "2_2") (pintype "input"))
      (node (ref "C19") (pin "2") (pinfunction "2_2") (pintype "input"))
      (node (ref "C23") (pin "2") (pinfunction "2_2") (pintype "input"))
      (node (ref "C24") (pin "2") (pinfunction "2_2") (pintype "input"))
      (node (ref "C25") (pin "2") (pinfunction "2_2") (pintype "unspecified"))
      (node (ref "C31") (pin "2") (pinfunction "2_2") (pintype "input"))
      (node (ref "C32") (pin "2") (pinfunction "2_2") (pintype "input"))
      (node (ref "C37") (pin "2") (pinfunction "2_2") (pintype "input"))
      (node (ref "C38") (pin "2") (pinfunction "2_2") (pintype "input"))
      (node (ref "LED2") (pin "2") (pinfunction "A_2") (pintype "input"))
      (node (ref "R2") (pin "13") (pinfunction "VDD_13") (pintype "unspecified"))
      (node (ref "R2") (pin "8") (pinfunction "VDDIO_8") (pintype "unspecified"))
      (node (ref "R20") (pin "2") (pinfunction "2_2") (pintype "input"))
      (node (ref "R21") (pin "2") (pinfunction "2_2") (pintype "input"))
      (node (ref "R5") (pin "2") (pinfunction "2_2") (pintype "input"))
      (node (ref "R6") (pin "2") (pinfunction "2_2") (pintype "input"))
      (node (ref "SW1") (pin "1") (pinfunction "1_1") (pintype "unspecified"))
      (node (ref "U2") (pin "1") (pinfunction "VBAT_1") (pintype "unspecified"))
      (node (ref "U2") (pin "13") (pinfunction "VDDA_13") (pintype "unspecified"))
      (node (ref "U2") (pin "19") (pinfunction "VDD_19") (pintype "unspecified"))
      (node (ref "U2") (pin "32") (pinfunction "VDD_32") (pintype "unspecified"))
      (node (ref "U2") (pin "48") (pinfunction "VDD_48") (pintype "unspecified"))
      (node (ref "U2") (pin "64") (pinfunction "VDD_64") (pintype "unspecified"))
      (node (ref "U4") (pin "8") (pinfunction "VCC_8") (pintype "unspecified"))
      (node (ref "U9") (pin "5") (pinfunction "VOUT_5") (pintype "unspecified"))
    )
    (net (code "2") (name "+5V") (class "Default")
      (node (ref "5V1") (pin "1") (pinfunction "pad_1") (pintype "unspecified"))
      (node (ref "5V2") (pin "1") (pinfunction "pad_1") (pintype "unspecified"))
      (node (ref "5V6") (pin "1") (pinfunction "pad_1") (pintype "unspecified"))
      (node (ref "5VTX") (pin "1") (pinfunction "pad_1") (pintype "unspecified"))
      (node (ref "B+1") (pin "1") (pinfunction "pad_1") (pintype "unspecified"))
      (node (ref "C4") (pin "2") (pinfunction "2_2") (pintype "unspecified"))
      (node (ref "CN1") (pin "4") (pinfunction "4_4") (pintype "unspecified"))
      (node (ref "D2") (pin "3") (pinfunction "K_3") (pintype "unspecified"))
      (node (ref "LED3") (pin "2") (pinfunction "A_2") (pintype "input"))
      (node (ref "U9") (pin "1") (pinfunction "VIN_1") (pintype "unspecified"))
      (node (ref "U9") (pin "3") (pinfunction "EN_3") (pintype "unspecified"))
    )
    (net (code "3") (name "+5VBAT") (class "Default")
      (node (ref "C14") (pin "2") (pinfunction "2_2") (pintype "input"))
      (node (ref "C15") (pin "2") (pinfunction "2_2") (pintype "input"))
      (node (ref "D2") (pin "1") (pinfunction "A_1") (pintype "unspecified"))
      (node (ref "L1") (pin "2") (pinfunction "2_2") (pintype "unspecified"))
      (node (ref "R29") (pin "2") (pinfunction "2_2") (pintype "unspecified"))
    )
    (net (code "4") (name "+5VBUS") (class "Default")
      (node (ref "D1") (pin "5") (pinfunction "VBUS_5") (pintype "input"))
      (node (ref "D2") (pin "2") (pinfunction "A_2") (pintype "unspecified"))
      (node (ref "USB1") (pin "11") (pinfunction "VBUS_11") (pintype "unspecified"))
      (node (ref "USB1") (pin "2") (pinfunction "VBUS_2") (pintype "unspecified"))
    )
    (net (code "5") (name "+9V") (class "Default")
      (node (ref "9V") (pin "1") (pinfunction "pad_1") (pintype "unspecified"))
      (node (ref "9V2") (pin "1") (pinfunction "pad_1") (pintype "unspecified"))
      (node (ref "9VTX") (pin "1") (pinfunction "pad_1") (pintype "unspecified"))
      (node (ref "C16") (pin "2") (pinfunction "2_2") (pintype "input"))
      (node (ref "C17") (pin "2") (pinfunction "2_2") (pintype "input"))
      (node (ref "L2") (pin "2") (pinfunction "2_2") (pintype "unspecified"))
      (node (ref "LED4") (pin "2") (pinfunction "A_2") (pintype "input"))
      (node (ref "R26") (pin "2") (pinfunction "2_2") (pintype "unspecified"))
      (node (ref "U10") (pin "6") (pinfunction "6_6") (pintype "unspecified"))
      (node (ref "U5") (pin "3") (pinfunction "3_3") (pintype "unspecified"))
    )
    (net (code "6") (name "+VLIPO") (class "Default")
      (node (ref "C22") (pin "2") (pinfunction "2_2") (pintype "input"))
      (node (ref "C3") (pin "2") (pinfunction "2_2") (pintype "input"))
      (node (ref "C5") (pin "2") (pinfunction "2_2") (pintype "input"))
      (node (ref "C6") (pin "2") (pinfunction "2_2") (pintype "input"))
      (node (ref "C7") (pin "2") (pinfunction "2_2") (pintype "input"))
      (node (ref "C8") (pin "2") (pinfunction "2_2") (pintype "input"))
      (node (ref "P1") (pin "7") (pinfunction "7_7") (pintype "unspecified"))
      (node (ref "R18") (pin "2") (pinfunction "2_2") (pintype "input"))
      (node (ref "R28") (pin "2") (pinfunction "2_2") (pintype "input"))
      (node (ref "R3") (pin "2") (pinfunction "2_2") (pintype "input"))
      (node (ref "U1") (pin "7") (pinfunction "IN_7") (pintype "unspecified"))
      (node (ref "U3") (pin "7") (pinfunction "IN_7") (pintype "unspecified"))
      (node (ref "VBAT1") (pin "1") (pinfunction "pad_1") (pintype "unspecified"))
    )
    (net (code "7") (name "ADC_CURR") (class "Default")
      (node (ref "CURR1") (pin "1") (pinfunction "pad_1") (pintype "unspecified"))
      (node (ref "P1") (pin "1") (pinfunction "1_1") (pintype "unspecified"))
      (node (ref "U2") (pin "9") (pinfunction "PC1_9") (pintype "unspecified"))
    )
    (net (code "8") (name "ADC_VBAT") (class "Default")
      (node (ref "R15") (pin "2") (pinfunction "2_2") (pintype "input"))
      (node (ref "R18") (pin "1") (pinfunction "1_1") (pintype "input"))
      (node (ref "U2") (pin "11") (pinfunction "PC3_11") (pintype "unspecified"))
    )
    (net (code "9") (name "BEEPER") (class "Default")
      (node (ref "Q3") (pin "1") (pinfunction "G_1") (pintype "unspecified"))
      (node (ref "U2") (pin "4") (pinfunction "PC15-OSC32_OUT_4") (pintype "unspecified"))
    )
    (net (code "10") (name "BOOT0") (class "Default")
      (node (ref "R11") (pin "2") (pinfunction "2_2") (pintype "input"))
      (node (ref "SW1") (pin "2") (pinfunction "2_2") (pintype "unspecified"))
      (node (ref "U2") (pin "60") (pinfunction "BOOT0_60") (pintype "unspecified"))
    )
    (net (code "11") (name "CS_FLASH") (class "Default")
      (node (ref "U2") (pin "41") (pinfunction "PA8_41") (pintype "unspecified"))
      (node (ref "U4") (pin "1") (pinfunction "CS#_1") (pintype "unspecified"))
    )
    (net (code "12") (name "CS_GYRO") (class "Default")
      (node (ref "R2") (pin "22") (pinfunction "nCS_22") (pintype "unspecified"))
      (node (ref "U2") (pin "20") (pinfunction "PA4_20") (pintype "unspecified"))
    )
    (net (code "13") (name "GND") (class "Default")
      (node (ref "C11") (pin "1") (pinfunction "1_1") (pintype "input"))
      (node (ref "C12") (pin "1") (pinfunction "1_1") (pintype "input"))
      (node (ref "C14") (pin "1") (pinfunction "1_1") (pintype "input"))
      (node (ref "C15") (pin "1") (pinfunction "1_1") (pintype "input"))
      (node (ref "C16") (pin "1") (pinfunction "1_1") (pintype "input"))
      (node (ref "C17") (pin "1") (pinfunction "1_1") (pintype "input"))
      (node (ref "C19") (pin "1") (pinfunction "1_1") (pintype "input"))
      (node (ref "C2") (pin "1") (pinfunction "1_1") (pintype "input"))
      (node (ref "C20") (pin "1") (pinfunction "1_1") (pintype "input"))
      (node (ref "C21") (pin "1") (pinfunction "1_1") (pintype "input"))
      (node (ref "C22") (pin "1") (pinfunction "1_1") (pintype "input"))
      (node (ref "C23") (pin "1") (pinfunction "1_1") (pintype "input"))
      (node (ref "C24") (pin "1") (pinfunction "1_1") (pintype "input"))
      (node (ref "C25") (pin "1") (pinfunction "1_1") (pintype "unspecified"))
      (node (ref "C3") (pin "1") (pinfunction "1_1") (pintype "input"))
      (node (ref "C31") (pin "1") (pinfunction "1_1") (pintype "input"))
      (node (ref "C32") (pin "1") (pinfunction "1_1") (pintype "input"))
      (node (ref "C37") (pin "1") (pinfunction "1_1") (pintype "input"))
      (node (ref "C38") (pin "1") (pinfunction "1_1") (pintype "input"))
      (node (ref "C4") (pin "1") (pinfunction "1_1") (pintype "unspecified"))
      (node (ref "C5") (pin "1") (pinfunction "1_1") (pintype "input"))
      (node (ref "C6") (pin "1") (pinfunction "1_1") (pintype "input"))
      (node (ref "C7") (pin "1") (pinfunction "1_1") (pintype "input"))
      (node (ref "C8") (pin "1") (pinfunction "1_1") (pintype "input"))
      (node (ref "C9") (pin "1") (pinfunction "1_1") (pintype "input"))
      (node (ref "CN1") (pin "3") (pinfunction "3_3") (pintype "unspecified"))
      (node (ref "CN1") (pin "5") (pinfunction "5_5") (pintype "unspecified"))
      (node (ref "CN1") (pin "6") (pinfunction "6_6") (pintype "unspecified"))
      (node (ref "D1") (pin "2") (pinfunction "GND_2") (pintype "input"))
      (node (ref "GND10") (pin "1") (pinfunction "pad_1") (pintype "unspecified"))
      (node (ref "GND3") (pin "1") (pinfunction "pad_1") (pintype "unspecified"))
      (node (ref "GND4") (pin "1") (pinfunction "pad_1") (pintype "unspecified"))
      (node (ref "GND5") (pin "1") (pinfunction "pad_1") (pintype "unspecified"))
      (node (ref "GND6") (pin "1") (pinfunction "pad_1") (pintype "unspecified"))
      (node (ref "GND8") (pin "1") (pinfunction "pad_1") (pintype "unspecified"))
      (node (ref "GND9") (pin "1") (pinfunction "pad_1") (pintype "unspecified"))
      (node (ref "P1") (pin "10") (pinfunction "10_10") (pintype "unspecified"))
      (node (ref "P1") (pin "8") (pinfunction "8_8") (pintype "unspecified"))
      (node (ref "P1") (pin "9") (pinfunction "9_9") (pintype "unspecified"))
      (node (ref "Q3") (pin "3") (pinfunction "D_3") (pintype "unspecified"))
      (node (ref "R1") (pin "1") (pinfunction "1_1") (pintype "input"))
      (node (ref "R11") (pin "1") (pinfunction "1_1") (pintype "input"))
      (node (ref "R13") (pin "1") (pinfunction "1_1") (pintype "input"))
      (node (ref "R14") (pin "1") (pinfunction "1_1") (pintype "input"))
      (node (ref "R15") (pin "1") (pinfunction "1_1") (pintype "input"))
      (node (ref "R16") (pin "1") (pinfunction "1_1") (pintype "input"))
      (node (ref "R17") (pin "1") (pinfunction "1_1") (pintype "input"))
      (node (ref "R19") (pin "2") (pinfunction "2_2") (pintype "input"))
      (node (ref "R2") (pin "11") (pinfunction "FSYNC_11") (pintype "unspecified"))
      (node (ref "R2") (pin "18") (pinfunction "GND_18") (pintype "unspecified"))
      (node (ref "R2") (pin "25") (pinfunction "EP_25") (pintype "unspecified"))
      (node (ref "R30") (pin "1") (pinfunction "1_1") (pintype "input"))
      (node (ref "R7") (pin "2") (pinfunction "2_2") (pintype "unspecified"))
      (node (ref "U1") (pin "5") (pinfunction "GND_5") (pintype "unspecified"))
      (node (ref "U10") (pin "2") (pinfunction "2_2") (pintype "unspecified"))
      (node (ref "U10") (pin "5") (pinfunction "5_5") (pintype "unspecified"))
      (node (ref "U10") (pin "7") (pinfunction "7_7") (pintype "unspecified"))
      (node (ref "U10") (pin "8") (pinfunction "8_8") (pintype "unspecified"))
      (node (ref "U2") (pin "12") (pinfunction "VSSA_12") (pintype "unspecified"))
      (node (ref "U2") (pin "18") (pinfunction "VSS_18") (pintype "unspecified"))
      (node (ref "U2") (pin "31") (pinfunction "VSS_31") (pintype "unspecified"))
      (node (ref "U2") (pin "47") (pinfunction "VSS_47") (pintype "unspecified"))
      (node (ref "U2") (pin "63") (pinfunction "VSS_63") (pintype "unspecified"))
      (node (ref "U3") (pin "5") (pinfunction "GND_5") (pintype "unspecified"))
      (node (ref "U4") (pin "4") (pinfunction "GND_4") (pintype "unspecified"))
      (node (ref "U5") (pin "2") (pinfunction "2_2") (pintype "unspecified"))
      (node (ref "U5") (pin "4") (pinfunction "4_4") (pintype "unspecified"))
      (node (ref "U5") (pin "5") (pinfunction "5_5") (pintype "unspecified"))
      (node (ref "U9") (pin "2") (pinfunction "GND_2") (pintype "unspecified"))
      (node (ref "USB1") (pin "1") (pinfunction "GND_1") (pintype "unspecified"))
      (node (ref "USB1") (pin "12") (pinfunction "GND_12") (pintype "unspecified"))
      (node (ref "X1") (pin "2") (pinfunction "GND_2") (pintype "input"))
    )
    (net (code "14") (name "I2C_SCL") (class "Default")
      (node (ref "R20") (pin "1") (pinfunction "1_1") (pintype "input"))
      (node (ref "SCL1") (pin "1") (pinfunction "pad_1") (pintype "unspecified"))
      (node (ref "U2") (pin "28") (pinfunction "PB10_28") (pintype "unspecified"))
    )
    (net (code "15") (name "I2C_SDA") (class "Default")
      (node (ref "R21") (pin "1") (pinfunction "1_1") (pintype "input"))
      (node (ref "SDA1") (pin "1") (pinfunction "pad_1") (pintype "unspecified"))
      (node (ref "U2") (pin "29") (pinfunction "PB11_29") (pintype "unspecified"))
    )
    (net (code "16") (name "INT_GYRO") (class "Default")
      (node (ref "R2") (pin "12") (pinfunction "INT_12") (pintype "unspecified"))
      (node (ref "U2") (pin "25") (pinfunction "PB0_25") (pintype "unspecified"))
    )
    (net (code "17") (name "LED0") (class "Default")
      (node (ref "LED1") (pin "1") (pinfunction "A_1") (pintype "input"))
      (node (ref "U2") (pin "46") (pinfunction "PA13_46") (pintype "unspecified"))
    )
    (net (code "18") (name "MOTOR1") (class "Default")
      (node (ref "M1") (pin "1") (pinfunction "pad_1") (pintype "unspecified"))
      (node (ref "P1") (pin "6") (pinfunction "6_6") (pintype "unspecified"))
      (node (ref "U2") (pin "56") (pinfunction "PB4_56") (pintype "unspecified"))
    )
    (net (code "19") (name "MOTOR2") (class "Default")
      (node (ref "M2") (pin "1") (pinfunction "pad_1") (pintype "unspecified"))
      (node (ref "P1") (pin "5") (pinfunction "5_5") (pintype "unspecified"))
      (node (ref "U2") (pin "55") (pinfunction "PB3_55") (pintype "unspecified"))
    )
    (net (code "20") (name "MOTOR3") (class "Default")
      (node (ref "M3") (pin "1") (pinfunction "pad_1") (pintype "unspecified"))
      (node (ref "P1") (pin "4") (pinfunction "4_4") (pintype "unspecified"))
      (node (ref "U2") (pin "38") (pinfunction "PC7_38") (pintype "unspecified"))
    )
    (net (code "21") (name "MOTOR4") (class "Default")
      (node (ref "M4") (pin "1") (pinfunction "pad_1") (pintype "unspecified"))
      (node (ref "P1") (pin "3") (pinfunction "3_3") (pintype "unspecified"))
      (node (ref "U2") (pin "37") (pinfunction "PC6_37") (pintype "unspecified"))
    )
    (net (code "22") (name "Net-(C13-Pad2)") (class "Default")
      (node (ref "C13") (pin "2") (pinfunction "2_2") (pintype "input"))
      (node (ref "R22") (pin "2") (pinfunction "2_2") (pintype "input"))
    )
    (net (code "23") (name "Net-(C18-Pad2)") (class "Default")
      (node (ref "C18") (pin "2") (pinfunction "2_2") (pintype "input"))
      (node (ref "R12") (pin "2") (pinfunction "2_2") (pintype "input"))
    )
    (net (code "24") (name "Net-(D1-I{slash}O1-Pad6)") (class "Default")
      (node (ref "D1") (pin "6") (pinfunction "I/O1_6") (pintype "input"))
      (node (ref "R8") (pin "1") (pinfunction "1_1") (pintype "input"))
    )
    (net (code "25") (name "Net-(D1-I{slash}O2-Pad4)") (class "Default")
      (node (ref "D1") (pin "4") (pinfunction "I/O2_4") (pintype "input"))
      (node (ref "R9") (pin "1") (pinfunction "1_1") (pintype "input"))
    )
    (net (code "26") (name "Net-(LED1-C)") (class "Default")
      (node (ref "LED1") (pin "2") (pinfunction "C_2") (pintype "input"))
      (node (ref "R16") (pin "2") (pinfunction "2_2") (pintype "input"))
    )
    (net (code "27") (name "Net-(LED2-C)") (class "Default")
      (node (ref "LED2") (pin "1") (pinfunction "C_1") (pintype "input"))
      (node (ref "R14") (pin "2") (pinfunction "2_2") (pintype "input"))
    )
    (net (code "28") (name "Net-(LED3-C)") (class "Default")
      (node (ref "LED3") (pin "1") (pinfunction "C_1") (pintype "input"))
      (node (ref "R17") (pin "2") (pinfunction "2_2") (pintype "input"))
    )
    (net (code "29") (name "Net-(LED4-C)") (class "Default")
      (node (ref "LED4") (pin "1") (pinfunction "C_1") (pintype "input"))
      (node (ref "R1") (pin "2") (pinfunction "2_2") (pintype "input"))
    )
    (net (code "30") (name "Net-(R2-REGOUT)") (class "Default")
      (node (ref "C2") (pin "2") (pinfunction "2_2") (pintype "input"))
      (node (ref "R2") (pin "10") (pinfunction "REGOUT_10") (pintype "unspecified"))
    )
    (net (code "31") (name "Net-(R10-Pad2)") (class "Default")
      (node (ref "R10") (pin "2") (pinfunction "2_2") (pintype "input"))
      (node (ref "R26") (pin "1") (pinfunction "1_1") (pintype "unspecified"))
      (node (ref "R7") (pin "1") (pinfunction "1_1") (pintype "unspecified"))
    )
    (net (code "32") (name "Net-(R24-Pad2)") (class "Default")
      (node (ref "R24") (pin "2") (pinfunction "2_2") (pintype "input"))
      (node (ref "R29") (pin "1") (pinfunction "1_1") (pintype "unspecified"))
      (node (ref "R30") (pin "2") (pinfunction "2_2") (pintype "input"))
    )
    (net (code "33") (name "Net-(U1-BST)") (class "Default")
      (node (ref "R12") (pin "1") (pinfunction "1_1") (pintype "input"))
      (node (ref "U1") (pin "4") (pinfunction "BST_4") (pintype "unspecified"))
    )
    (net (code "34") (name "Net-(U1-EN{slash}SYNC)") (class "Default")
      (node (ref "R28") (pin "1") (pinfunction "1_1") (pintype "input"))
      (node (ref "U1") (pin "3") (pinfunction "EN/SYNC_3") (pintype "unspecified"))
    )
    (net (code "35") (name "Net-(U1-FB)") (class "Default")
      (node (ref "R10") (pin "1") (pinfunction "1_1") (pintype "input"))
      (node (ref "U1") (pin "1") (pinfunction "FB_1") (pintype "unspecified"))
    )
    (net (code "36") (name "Net-(U1-PG)") (class "Default")
      (node (ref "R27") (pin "2") (pinfunction "2_2") (pintype "input"))
      (node (ref "U1") (pin "8") (pinfunction "PG_8") (pintype "unspecified"))
    )
    (net (code "37") (name "Net-(U1-SW)") (class "Default")
      (node (ref "C18") (pin "1") (pinfunction "1_1") (pintype "input"))
      (node (ref "L2") (pin "1") (pinfunction "1_1") (pintype "unspecified"))
      (node (ref "U1") (pin "6") (pinfunction "SW_6") (pintype "unspecified"))
    )
    (net (code "38") (name "Net-(U1-VCC)") (class "Default")
      (node (ref "C21") (pin "2") (pinfunction "2_2") (pintype "input"))
      (node (ref "R27") (pin "1") (pinfunction "1_1") (pintype "input"))
      (node (ref "U1") (pin "2") (pinfunction "VCC_2") (pintype "unspecified"))
    )
    (net (code "39") (name "Net-(U2-PH0-OSC_IN)") (class "Default")
      (node (ref "U2") (pin "5") (pinfunction "PH0-OSC_IN_5") (pintype "unspecified"))
      (node (ref "X1") (pin "3") (pinfunction "OSC2_3") (pintype "input"))
    )
    (net (code "40") (name "Net-(U2-PH1-OSC_OUT)") (class "Default")
      (node (ref "U2") (pin "6") (pinfunction "PH1-OSC_OUT_6") (pintype "unspecified"))
      (node (ref "X1") (pin "1") (pinfunction "OSC1_1") (pintype "input"))
    )
    (net (code "41") (name "Net-(U2-VCAP_1)") (class "Default")
      (node (ref "C20") (pin "2") (pinfunction "2_2") (pintype "input"))
      (node (ref "U2") (pin "30") (pinfunction "VCAP_1_30") (pintype "unspecified"))
    )
    (net (code "42") (name "Net-(U3-BST)") (class "Default")
      (node (ref "R22") (pin "1") (pinfunction "1_1") (pintype "input"))
      (node (ref "U3") (pin "4") (pinfunction "BST_4") (pintype "unspecified"))
    )
    (net (code "43") (name "Net-(U3-EN{slash}SYNC)") (class "Default")
      (node (ref "R3") (pin "1") (pinfunction "1_1") (pintype "input"))
      (node (ref "U3") (pin "3") (pinfunction "EN/SYNC_3") (pintype "unspecified"))
    )
    (net (code "44") (name "Net-(U3-FB)") (class "Default")
      (node (ref "R24") (pin "1") (pinfunction "1_1") (pintype "input"))
      (node (ref "U3") (pin "1") (pinfunction "FB_1") (pintype "unspecified"))
    )
    (net (code "45") (name "Net-(U3-PG)") (class "Default")
      (node (ref "R4") (pin "2") (pinfunction "2_2") (pintype "input"))
      (node (ref "U3") (pin "8") (pinfunction "PG_8") (pintype "unspecified"))
    )
    (net (code "46") (name "Net-(U3-SW)") (class "Default")
      (node (ref "C13") (pin "1") (pinfunction "1_1") (pintype "input"))
      (node (ref "L1") (pin "1") (pinfunction "1_1") (pintype "unspecified"))
      (node (ref "U3") (pin "6") (pinfunction "SW_6") (pintype "unspecified"))
    )
    (net (code "47") (name "Net-(U3-VCC)") (class "Default")
      (node (ref "C9") (pin "2") (pinfunction "2_2") (pintype "input"))
      (node (ref "R4") (pin "1") (pinfunction "1_1") (pintype "input"))
      (node (ref "U3") (pin "2") (pinfunction "VCC_2") (pintype "unspecified"))
    )
    (net (code "48") (name "Net-(U4-IO2)") (class "Default")
      (node (ref "R5") (pin "1") (pinfunction "1_1") (pintype "input"))
      (node (ref "U4") (pin "3") (pinfunction "IO2_3") (pintype "unspecified"))
    )
    (net (code "49") (name "Net-(U4-IO3)") (class "Default")
      (node (ref "R6") (pin "1") (pinfunction "1_1") (pintype "input"))
      (node (ref "U4") (pin "7") (pinfunction "IO3_7") (pintype "unspecified"))
    )
    (net (code "50") (name "Net-(USB1-CC1)") (class "Default")
      (node (ref "R13") (pin "2") (pinfunction "2_2") (pintype "input"))
      (node (ref "USB1") (pin "4") (pinfunction "CC1_4") (pintype "unspecified"))
    )
    (net (code "51") (name "Net-(USB1-CC2)") (class "Default")
      (node (ref "R19") (pin "1") (pinfunction "1_1") (pintype "input"))
      (node (ref "USB1") (pin "10") (pinfunction "CC2_10") (pintype "unspecified"))
    )
    (net (code "52") (name "PIN_B-") (class "Default")
      (node (ref "B-1") (pin "1") (pinfunction "pad_1") (pintype "unspecified"))
      (node (ref "Q3") (pin "2") (pinfunction "S_2") (pintype "unspecified"))
    )
    (net (code "53") (name "SPI1_MISO") (class "Default")
      (node (ref "R2") (pin "24") (pinfunction "SDA/SDI_24") (pintype "unspecified"))
      (node (ref "U2") (pin "23") (pinfunction "PA7_23") (pintype "unspecified"))
    )
    (net (code "54") (name "SPI1_MOSI") (class "Default")
      (node (ref "R2") (pin "9") (pinfunction "AD0/SDO_9") (pintype "unspecified"))
      (node (ref "U2") (pin "22") (pinfunction "PA6_22") (pintype "unspecified"))
    )
    (net (code "55") (name "SPI1_SCK") (class "Default")
      (node (ref "R2") (pin "23") (pinfunction "SCL/SCLK_23") (pintype "unspecified"))
      (node (ref "U2") (pin "21") (pinfunction "PA5_21") (pintype "unspecified"))
    )
    (net (code "56") (name "SPI2_MISO") (class "Default")
      (node (ref "U2") (pin "36") (pinfunction "PB15_36") (pintype "unspecified"))
      (node (ref "U4") (pin "2") (pinfunction "DO_2") (pintype "unspecified"))
    )
    (net (code "57") (name "SPI2_MOSI") (class "Default")
      (node (ref "U2") (pin "35") (pinfunction "PB14_35") (pintype "unspecified"))
      (node (ref "U4") (pin "5") (pinfunction "DI_5") (pintype "unspecified"))
    )
    (net (code "58") (name "SPI2_SCK") (class "Default")
      (node (ref "U2") (pin "34") (pinfunction "PB13_34") (pintype "unspecified"))
      (node (ref "U4") (pin "6") (pinfunction "CLK_6") (pintype "unspecified"))
    )
    (net (code "59") (name "UART1_RX") (class "Default")
      (node (ref "RX1") (pin "1") (pinfunction "pad_1") (pintype "unspecified"))
      (node (ref "U10") (pin "1") (pinfunction "1_1") (pintype "unspecified"))
      (node (ref "U2") (pin "59") (pinfunction "PB7_59") (pintype "unspecified"))
    )
    (net (code "60") (name "UART1_TX") (class "Default")
      (node (ref "TX1") (pin "1") (pinfunction "pad_1") (pintype "unspecified"))
      (node (ref "U2") (pin "58") (pinfunction "PB6_58") (pintype "unspecified"))
    )
    (net (code "61") (name "UART2_RX") (class "Default")
      (node (ref "RX2") (pin "1") (pinfunction "pad_1") (pintype "unspecified"))
      (node (ref "U10") (pin "3") (pinfunction "3_3") (pintype "unspecified"))
      (node (ref "U2") (pin "17") (pinfunction "PA3_17") (pintype "unspecified"))
    )
    (net (code "62") (name "UART2_TX") (class "Default")
      (node (ref "CN1") (pin "2") (pinfunction "2_2") (pintype "unspecified"))
      (node (ref "TX2") (pin "1") (pinfunction "pad_1") (pintype "unspecified"))
      (node (ref "TX2A") (pin "1") (pinfunction "pad_1") (pintype "unspecified"))
      (node (ref "U10") (pin "4") (pinfunction "4_4") (pintype "unspecified"))
      (node (ref "U2") (pin "16") (pinfunction "PA2_16") (pintype "unspecified"))
    )
    (net (code "63") (name "UART3_RX") (class "Default")
      (node (ref "P1") (pin "2") (pinfunction "2_2") (pintype "unspecified"))
      (node (ref "RX5") (pin "1") (pinfunction "pad_1") (pintype "unspecified"))
      (node (ref "U2") (pin "52") (pinfunction "PC11_52") (pintype "unspecified"))
    )
    (net (code "64") (name "UART3_TX") (class "Default")
      (node (ref "TX5") (pin "1") (pinfunction "pad_1") (pintype "unspecified"))
      (node (ref "U2") (pin "51") (pinfunction "PC10_51") (pintype "unspecified"))
    )
    (net (code "65") (name "UART4_RX") (class "Default")
      (node (ref "RX6") (pin "1") (pinfunction "pad_1") (pintype "unspecified"))
      (node (ref "U2") (pin "15") (pinfunction "PA1_15") (pintype "unspecified"))
    )
    (net (code "66") (name "UART4_TX") (class "Default")
      (node (ref "TX6") (pin "1") (pinfunction "pad_1") (pintype "unspecified"))
      (node (ref "U2") (pin "14") (pinfunction "PA0-WKUP_14") (pintype "unspecified"))
    )
    (net (code "67") (name "UART5_RX") (class "Default")
      (node (ref "RX3") (pin "1") (pinfunction "pad_1") (pintype "unspecified"))
      (node (ref "U2") (pin "43") (pinfunction "PA10_43") (pintype "unspecified"))
    )
    (net (code "68") (name "UART5_TX") (class "Default")
      (node (ref "TX3") (pin "1") (pinfunction "pad_1") (pintype "unspecified"))
      (node (ref "U2") (pin "42") (pinfunction "PA9_42") (pintype "unspecified"))
    )
    (net (code "69") (name "USB_CON_D+") (class "Default")
      (node (ref "D1") (pin "3") (pinfunction "I/O2_3") (pintype "input"))
      (node (ref "USB1") (pin "6") (pinfunction "DP1_6") (pintype "unspecified"))
      (node (ref "USB1") (pin "8") (pinfunction "DP2_8") (pintype "unspecified"))
    )
    (net (code "70") (name "USB_CON_D-") (class "Default")
      (node (ref "D1") (pin "1") (pinfunction "I/O1_1") (pintype "input"))
      (node (ref "USB1") (pin "5") (pinfunction "DN2_5") (pintype "unspecified"))
      (node (ref "USB1") (pin "7") (pinfunction "DN1_7") (pintype "unspecified"))
    )
    (net (code "71") (name "USB_D+") (class "Default")
      (node (ref "R9") (pin "2") (pinfunction "2_2") (pintype "input"))
      (node (ref "U2") (pin "45") (pinfunction "PA12_45") (pintype "unspecified"))
    )
    (net (code "72") (name "USB_D-") (class "Default")
      (node (ref "R8") (pin "2") (pinfunction "2_2") (pintype "input"))
      (node (ref "U2") (pin "44") (pinfunction "PA11_44") (pintype "unspecified"))
    )
    (net (code "73") (name "VIDEO") (class "Default")
      (node (ref "CAM1") (pin "1") (pinfunction "pad_1") (pintype "unspecified"))
      (node (ref "CN1") (pin "1") (pinfunction "1_1") (pintype "unspecified"))
      (node (ref "U5") (pin "1") (pinfunction "1_1") (pintype "unspecified"))
      (node (ref "VTX1") (pin "1") (pinfunction "pad_1") (pintype "unspecified"))
    )
    (net (code "74") (name "unconnected-(R2-NC-Pad1)") (class "Default")
      (node (ref "R2") (pin "1") (pinfunction "NC_1") (pintype "unspecified+no_connect"))
    )
    (net (code "75") (name "unconnected-(R2-NC-Pad2)") (class "Default")
      (node (ref "R2") (pin "2") (pinfunction "NC_2") (pintype "unspecified+no_connect"))
    )
    (net (code "76") (name "unconnected-(R2-NC-Pad3)") (class "Default")
      (node (ref "R2") (pin "3") (pinfunction "NC_3") (pintype "unspecified+no_connect"))
    )
    (net (code "77") (name "unconnected-(R2-NC-Pad4)") (class "Default")
      (node (ref "R2") (pin "4") (pinfunction "NC_4") (pintype "unspecified+no_connect"))
    )
    (net (code "78") (name "unconnected-(R2-NC-Pad5)") (class "Default")
      (node (ref "R2") (pin "5") (pinfunction "NC_5") (pintype "unspecified+no_connect"))
    )
    (net (code "79") (name "unconnected-(R2-NC-Pad6)") (class "Default")
      (node (ref "R2") (pin "6") (pinfunction "NC_6") (pintype "unspecified+no_connect"))
    )
    (net (code "80") (name "unconnected-(R2-NC-Pad7)") (class "Default")
      (node (ref "R2") (pin "7") (pinfunction "NC_7") (pintype "unspecified+no_connect"))
    )
    (net (code "81") (name "unconnected-(R2-NC-Pad14)") (class "Default")
      (node (ref "R2") (pin "14") (pinfunction "NC_14") (pintype "unspecified+no_connect"))
    )
    (net (code "82") (name "unconnected-(R2-NC-Pad15)") (class "Default")
      (node (ref "R2") (pin "15") (pinfunction "NC_15") (pintype "unspecified+no_connect"))
    )
    (net (code "83") (name "unconnected-(R2-NC-Pad16)") (class "Default")
      (node (ref "R2") (pin "16") (pinfunction "NC_16") (pintype "unspecified+no_connect"))
    )
    (net (code "84") (name "unconnected-(R2-NC-Pad17)") (class "Default")
      (node (ref "R2") (pin "17") (pinfunction "NC_17") (pintype "unspecified+no_connect"))
    )
    (net (code "85") (name "unconnected-(R2-NC-Pad19)") (class "Default")
      (node (ref "R2") (pin "19") (pinfunction "NC_19") (pintype "unspecified+no_connect"))
    )
    (net (code "86") (name "unconnected-(R2-NC-Pad20)") (class "Default")
      (node (ref "R2") (pin "20") (pinfunction "NC_20") (pintype "unspecified+no_connect"))
    )
    (net (code "87") (name "unconnected-(R2-NC-Pad21)") (class "Default")
      (node (ref "R2") (pin "21") (pinfunction "NC_21") (pintype "unspecified+no_connect"))
    )
    (net (code "88") (name "unconnected-(U2-NRST-Pad7)") (class "Default")
      (node (ref "U2") (pin "7") (pinfunction "NRST_7") (pintype "unspecified+no_connect"))
    )
    (net (code "89") (name "unconnected-(U2-PA14-Pad49)") (class "Default")
      (node (ref "U2") (pin "49") (pinfunction "PA14_49") (pintype "unspecified+no_connect"))
    )
    (net (code "90") (name "unconnected-(U2-PA15-Pad50)") (class "Default")
      (node (ref "U2") (pin "50") (pinfunction "PA15_50") (pintype "unspecified+no_connect"))
    )
    (net (code "91") (name "unconnected-(U2-PB1-Pad26)") (class "Default")
      (node (ref "U2") (pin "26") (pinfunction "PB1_26") (pintype "unspecified+no_connect"))
    )
    (net (code "92") (name "unconnected-(U2-PB2-Pad27)") (class "Default")
      (node (ref "U2") (pin "27") (pinfunction "PB2_27") (pintype "unspecified+no_connect"))
    )
    (net (code "93") (name "unconnected-(U2-PB5-Pad57)") (class "Default")
      (node (ref "U2") (pin "57") (pinfunction "PB5_57") (pintype "unspecified+no_connect"))
    )
    (net (code "94") (name "unconnected-(U2-PB8-Pad61)") (class "Default")
      (node (ref "U2") (pin "61") (pinfunction "PB8_61") (pintype "unspecified+no_connect"))
    )
    (net (code "95") (name "unconnected-(U2-PB9-Pad62)") (class "Default")
      (node (ref "U2") (pin "62") (pinfunction "PB9_62") (pintype "unspecified+no_connect"))
    )
    (net (code "96") (name "unconnected-(U2-PB12-Pad33)") (class "Default")
      (node (ref "U2") (pin "33") (pinfunction "PB12_33") (pintype "unspecified+no_connect"))
    )
    (net (code "97") (name "unconnected-(U2-PC0-Pad8)") (class "Default")
      (node (ref "U2") (pin "8") (pinfunction "PC0_8") (pintype "unspecified+no_connect"))
    )
    (net (code "98") (name "unconnected-(U2-PC2-Pad10)") (class "Default")
      (node (ref "U2") (pin "10") (pinfunction "PC2_10") (pintype "unspecified+no_connect"))
    )
    (net (code "99") (name "unconnected-(U2-PC4-Pad24)") (class "Default")
      (node (ref "U2") (pin "24") (pinfunction "PC4_24") (pintype "unspecified+no_connect"))
    )
    (net (code "100") (name "unconnected-(U2-PC8-Pad39)") (class "Default")
      (node (ref "U2") (pin "39") (pinfunction "PC8_39") (pintype "unspecified+no_connect"))
    )
    (net (code "101") (name "unconnected-(U2-PC9-Pad40)") (class "Default")
      (node (ref "U2") (pin "40") (pinfunction "PC9_40") (pintype "unspecified+no_connect"))
    )
    (net (code "102") (name "unconnected-(U2-PC12-Pad53)") (class "Default")
      (node (ref "U2") (pin "53") (pinfunction "PC12_53") (pintype "unspecified+no_connect"))
    )
    (net (code "103") (name "unconnected-(U2-PC13-Pad2)") (class "Default")
      (node (ref "U2") (pin "2") (pinfunction "PC13_2") (pintype "unspecified+no_connect"))
    )
    (net (code "104") (name "unconnected-(U2-PC14-OSC32_IN-Pad3)") (class "Default")
      (node (ref "U2") (pin "3") (pinfunction "PC14-OSC32_IN_3") (pintype "unspecified+no_connect"))
    )
    (net (code "105") (name "unconnected-(U2-PD2-Pad54)") (class "Default")
      (node (ref "U2") (pin "54") (pinfunction "PD2_54") (pintype "unspecified+no_connect"))
    )
    (net (code "106") (name "unconnected-(U9-NC-Pad4)") (class "Default")
      (node (ref "U9") (pin "4") (pinfunction "NC_4") (pintype "unspecified+no_connect"))
    )
    (net (code "107") (name "unconnected-(USB1-SBU1-Pad9)") (class "Default")
      (node (ref "USB1") (pin "9") (pinfunction "SBU1_9") (pintype "unspecified+no_connect"))
    )
    (net (code "108") (name "unconnected-(USB1-SBU2-Pad3)") (class "Default")
      (node (ref "USB1") (pin "3") (pinfunction "SBU2_3") (pintype "unspecified+no_connect"))
    )
    (net (code "109") (name "unconnected-(USB1-SHELL-Pad13)") (class "Default")
      (node (ref "USB1") (pin "13") (pinfunction "SHELL_13") (pintype "unspecified+no_connect"))
    )
    (net (code "110") (name "unconnected-(USB1-SHELL-Pad14)") (class "Default")
      (node (ref "USB1") (pin "14") (pinfunction "SHELL_14") (pintype "unspecified+no_connect"))
    )
  )
)
